# BigClown_GPS_Teseo-LIV3F_module_v1_0.net
KiCad netlist of a schematic drawn in EAGLE
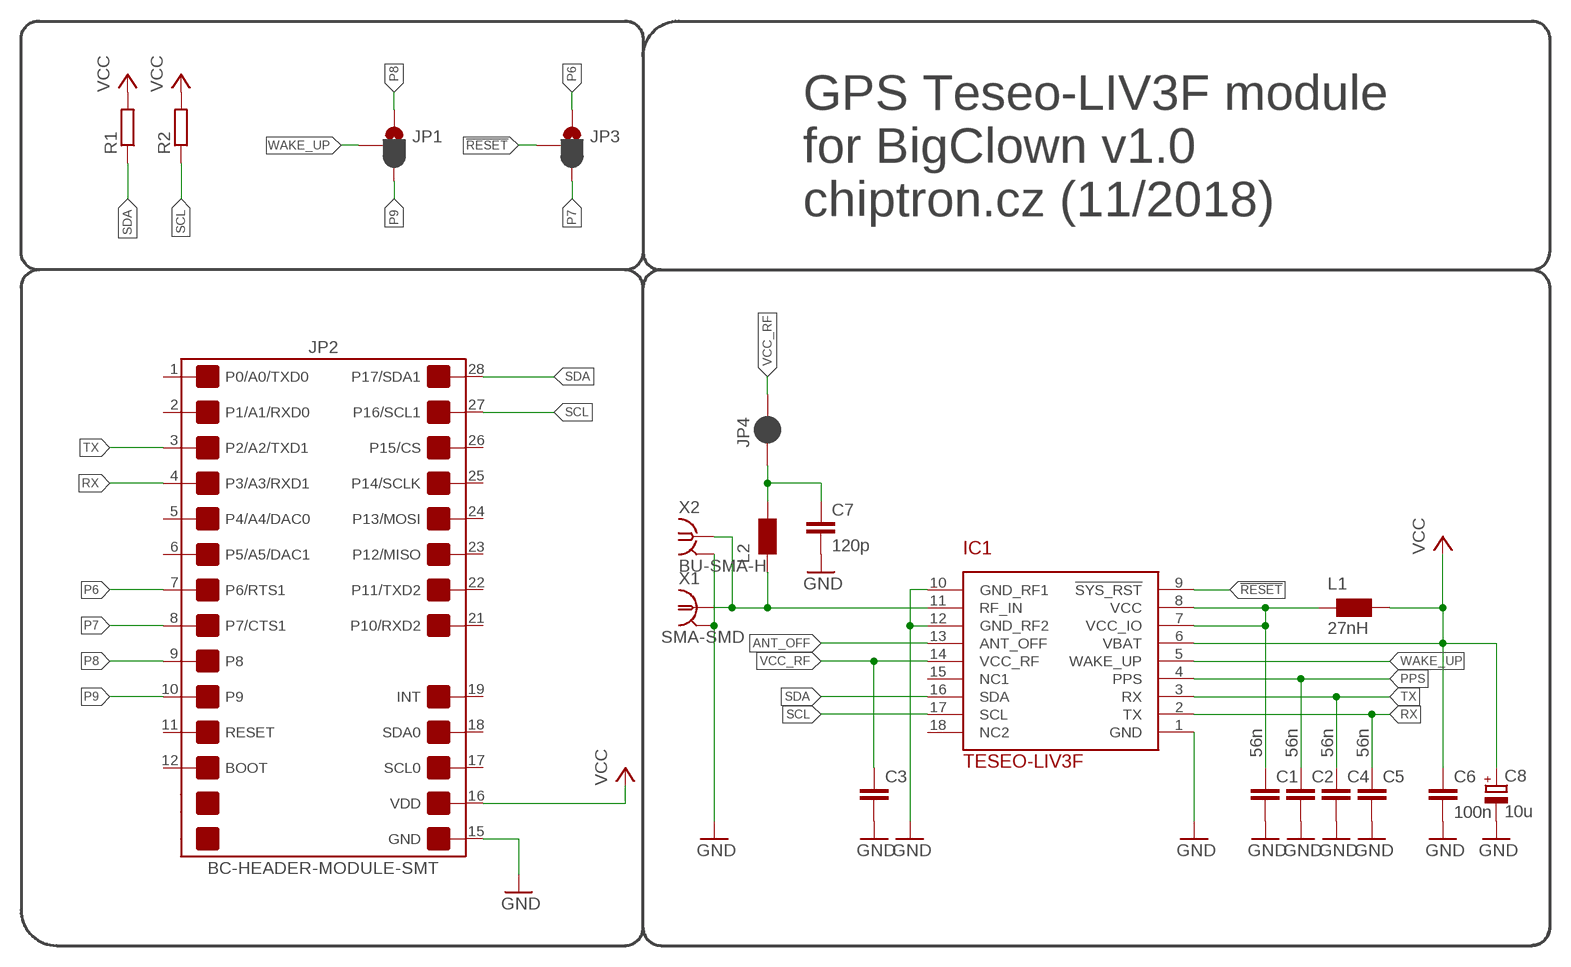
[diagram p0: schematic, sheet 1]

(export (version "E")
  (design (tool "Eeschema 10.0.6"))
  (components
    (comp (ref "C1")
      (value "56n")
      (footprint "eagle-import:C0805")
      (libsource (lib "eagle-import") (part "C-EUC0805"))
    )
    (comp (ref "C2")
      (value "56n")
      (footprint "eagle-import:C0805")
      (libsource (lib "eagle-import") (part "C-EUC0805"))
    )
    (comp (ref "C3")
      (value "C-EUC0805")
      (footprint "eagle-import:C0805")
      (libsource (lib "eagle-import") (part "C-EUC0805"))
    )
    (comp (ref "C4")
      (value "56n")
      (footprint "eagle-import:C0805")
      (libsource (lib "eagle-import") (part "C-EUC0805"))
    )
    (comp (ref "C5")
      (value "56n")
      (footprint "eagle-import:C0805")
      (libsource (lib "eagle-import") (part "C-EUC0805"))
    )
    (comp (ref "C6")
      (value "100n")
      (footprint "eagle-import:C0805")
      (libsource (lib "eagle-import") (part "C-EUC0805"))
    )
    (comp (ref "C7")
      (value "120p")
      (footprint "eagle-import:C0805")
      (libsource (lib "eagle-import") (part "C-EUC0805"))
    )
    (comp (ref "C8")
      (value "10u")
      (footprint "eagle-import:SMC_B")
      (libsource (lib "eagle-import") (part "CPOL-EUSMCB"))
    )
    (comp (ref "IC1")
      (value "TESEO-LIV3F")
      (footprint "eagle-import:TESEO-LIV3F")
      (libsource (lib "eagle-import") (part "TESEO-LIV3F"))
    )
    (comp (ref "JP1")
      (value "JUMPER-SMT_3_1-NC_PASTE_SILK")
      (footprint "eagle-import:SMT-JUMPER_3_1-NC_PASTE_SILK")
      (libsource (lib "eagle-import") (part "JUMPER-SMT_3_1-NC_PASTE_SILK"))
    )
    (comp (ref "JP2")
      (value "BC-HEADER-MODULE-SMT")
      (footprint "eagle-import:BC-HEADER-MODULE-SMT")
      (libsource (lib "eagle-import") (part "BC-HEADER-MODULE-SMT"))
    )
    (comp (ref "JP3")
      (value "JUMPER-SMT_3_1-NC_PASTE_SILK")
      (footprint "eagle-import:SMT-JUMPER_3_1-NC_PASTE_SILK")
      (libsource (lib "eagle-import") (part "JUMPER-SMT_3_1-NC_PASTE_SILK"))
    )
    (comp (ref "JP4")
      (value "JUMPER-SMT_2_NC_PASTE_SILK")
      (footprint "eagle-import:SMT-JUMPER_2_NC_PASTE_SILK")
      (libsource (lib "eagle-import") (part "JUMPER-SMT_2_NC_PASTE_SILK"))
    )
    (comp (ref "L1")
      (value "27nH")
      (footprint "eagle-import:0805")
      (libsource (lib "eagle-import") (part "WE-MK_0805"))
    )
    (comp (ref "L2")
      (value "33nF")
      (footprint "eagle-import:0805")
      (libsource (lib "eagle-import") (part "WE-MK_0805"))
    )
    (comp (ref "R1")
      (value "R-EU_M0805")
      (footprint "eagle-import:M0805")
      (libsource (lib "eagle-import") (part "R-EU_M0805"))
    )
    (comp (ref "R2")
      (value "R-EU_M0805")
      (footprint "eagle-import:M0805")
      (libsource (lib "eagle-import") (part "R-EU_M0805"))
    )
    (comp (ref "X1")
      (value "SMA-SMD")
      (footprint "eagle-import:SMA-SMD")
      (libsource (lib "eagle-import") (part "SMA-SMD"))
    )
    (comp (ref "X2")
      (value "BU-SMA-H")
      (footprint "eagle-import:BU-SMA-H")
      (libsource (lib "eagle-import") (part "BU-SMA-H"))
    )
  )
  (nets
    (net (code "1") (name "/~{RESET}") (class "Default")
      (node (ref "IC1") (pin "9") (pinfunction "~{SYS_RST}_9") (pintype "bidirectional"))
      (node (ref "JP3") (pin "2") (pinfunction "2_2") (pintype "passive"))
    )
    (net (code "2") (name "ANT_OFF") (class "Default")
      (node (ref "IC1") (pin "13") (pinfunction "ANT_OFF_13") (pintype "output"))
    )
    (net (code "3") (name "GND") (class "Default")
      (node (ref "C1") (pin "2") (pinfunction "2_2") (pintype "passive"))
      (node (ref "C2") (pin "2") (pinfunction "2_2") (pintype "passive"))
      (node (ref "C3") (pin "2") (pinfunction "2_2") (pintype "passive"))
      (node (ref "C4") (pin "2") (pinfunction "2_2") (pintype "passive"))
      (node (ref "C5") (pin "2") (pinfunction "2_2") (pintype "passive"))
      (node (ref "C6") (pin "2") (pinfunction "2_2") (pintype "passive"))
      (node (ref "C7") (pin "2") (pinfunction "2_2") (pintype "passive"))
      (node (ref "C8") (pin "-") (pinfunction "-_-") (pintype "passive"))
      (node (ref "IC1") (pin "1") (pinfunction "GND_1") (pintype "power_in"))
      (node (ref "IC1") (pin "10") (pinfunction "GND_RF1_10") (pintype "power_in"))
      (node (ref "IC1") (pin "12") (pinfunction "GND_RF2_12") (pintype "power_in"))
      (node (ref "JP2") (pin "15") (pinfunction "GND_15") (pintype "passive"))
      (node (ref "X1") (pin "2@1") (pinfunction "2_2@1") (pintype "passive"))
      (node (ref "X1") (pin "2@2") (pinfunction "2_2@2") (pintype "passive"))
      (node (ref "X1") (pin "2@3") (pinfunction "2_2@3") (pintype "passive"))
      (node (ref "X1") (pin "2@4") (pinfunction "2_2@4") (pintype "passive"))
      (node (ref "X1") (pin "2@5") (pinfunction "2_2@5") (pintype "passive"))
      (node (ref "X1") (pin "2@6") (pinfunction "2_2@6") (pintype "passive"))
      (node (ref "X2") (pin "2") (pinfunction "2_2") (pintype "passive"))
      (node (ref "X2") (pin "3") (pinfunction "2_3") (pintype "passive"))
      (node (ref "X2") (pin "4") (pinfunction "2_4") (pintype "passive"))
      (node (ref "X2") (pin "5") (pinfunction "2_5") (pintype "passive"))
    )
    (net (code "4") (name "Net-(C7-Pad1)") (class "Default")
      (node (ref "C7") (pin "1") (pinfunction "1_1") (pintype "passive"))
      (node (ref "JP4") (pin "1") (pinfunction "1_1") (pintype "passive"))
      (node (ref "L2") (pin "2") (pinfunction "2_2") (pintype "passive"))
    )
    (net (code "5") (name "Net-(IC1-RF_IN)") (class "Default")
      (node (ref "IC1") (pin "11") (pinfunction "RF_IN_11") (pintype "input"))
      (node (ref "L2") (pin "1") (pinfunction "1_1") (pintype "passive"))
      (node (ref "X1") (pin "1") (pinfunction "1_1") (pintype "passive"))
      (node (ref "X2") (pin "1") (pinfunction "1_1") (pintype "passive"))
    )
    (net (code "6") (name "Net-(IC1-VCC)") (class "Default")
      (node (ref "C1") (pin "1") (pinfunction "1_1") (pintype "passive"))
      (node (ref "IC1") (pin "7") (pinfunction "VCC_IO_7") (pintype "power_in"))
      (node (ref "IC1") (pin "8") (pinfunction "VCC_8") (pintype "power_in"))
      (node (ref "L1") (pin "1") (pinfunction "1_1") (pintype "passive"))
    )
    (net (code "7") (name "P6") (class "Default")
      (node (ref "JP2") (pin "7") (pinfunction "P6/RTS1_7") (pintype "passive"))
      (node (ref "JP3") (pin "1") (pinfunction "1_1") (pintype "passive"))
    )
    (net (code "8") (name "P7") (class "Default")
      (node (ref "JP2") (pin "8") (pinfunction "P7/CTS1_8") (pintype "passive"))
      (node (ref "JP3") (pin "3") (pinfunction "3_3") (pintype "passive"))
    )
    (net (code "9") (name "P8") (class "Default")
      (node (ref "JP1") (pin "1") (pinfunction "1_1") (pintype "passive"))
      (node (ref "JP2") (pin "9") (pinfunction "P8_9") (pintype "passive"))
    )
    (net (code "10") (name "P9") (class "Default")
      (node (ref "JP1") (pin "3") (pinfunction "3_3") (pintype "passive"))
      (node (ref "JP2") (pin "10") (pinfunction "P9_10") (pintype "passive"))
    )
    (net (code "11") (name "PPS") (class "Default")
      (node (ref "C2") (pin "1") (pinfunction "1_1") (pintype "passive"))
      (node (ref "IC1") (pin "4") (pinfunction "PPS_4") (pintype "output"))
    )
    (net (code "12") (name "RX") (class "Default")
      (node (ref "C5") (pin "1") (pinfunction "1_1") (pintype "passive"))
      (node (ref "IC1") (pin "2") (pinfunction "TX_2") (pintype "bidirectional"))
      (node (ref "JP2") (pin "4") (pinfunction "P3/A3/RXD1_4") (pintype "passive"))
    )
    (net (code "13") (name "SCL") (class "Default")
      (node (ref "IC1") (pin "17") (pinfunction "SCL_17") (pintype "bidirectional"))
      (node (ref "JP2") (pin "27") (pinfunction "P16/SCL1_27") (pintype "passive"))
      (node (ref "R2") (pin "1") (pinfunction "1_1") (pintype "passive"))
    )
    (net (code "14") (name "SDA") (class "Default")
      (node (ref "IC1") (pin "16") (pinfunction "SDA_16") (pintype "bidirectional"))
      (node (ref "JP2") (pin "28") (pinfunction "P17/SDA1_28") (pintype "passive"))
      (node (ref "R1") (pin "1") (pinfunction "1_1") (pintype "passive"))
    )
    (net (code "15") (name "TX") (class "Default")
      (node (ref "C4") (pin "1") (pinfunction "1_1") (pintype "passive"))
      (node (ref "IC1") (pin "3") (pinfunction "RX_3") (pintype "bidirectional"))
      (node (ref "JP2") (pin "3") (pinfunction "P2/A2/TXD1_3") (pintype "passive"))
    )
    (net (code "16") (name "VCC") (class "Default")
      (node (ref "C6") (pin "1") (pinfunction "1_1") (pintype "passive"))
      (node (ref "C8") (pin "+") (pinfunction "+_+") (pintype "passive"))
      (node (ref "IC1") (pin "6") (pinfunction "VBAT_6") (pintype "power_in"))
      (node (ref "JP2") (pin "16") (pinfunction "VDD_16") (pintype "passive"))
      (node (ref "L1") (pin "2") (pinfunction "2_2") (pintype "passive"))
      (node (ref "R1") (pin "2") (pinfunction "2_2") (pintype "passive"))
      (node (ref "R2") (pin "2") (pinfunction "2_2") (pintype "passive"))
    )
    (net (code "17") (name "VCC_RF") (class "Default")
      (node (ref "C3") (pin "1") (pinfunction "1_1") (pintype "passive"))
      (node (ref "IC1") (pin "14") (pinfunction "VCC_RF_14") (pintype "power_in"))
      (node (ref "JP4") (pin "2") (pinfunction "2_2") (pintype "passive"))
    )
    (net (code "18") (name "WAKE_UP") (class "Default")
      (node (ref "IC1") (pin "5") (pinfunction "WAKE_UP_5") (pintype "input"))
      (node (ref "JP1") (pin "2") (pinfunction "2_2") (pintype "passive"))
    )
    (net (code "19") (name "unconnected-(IC1-NC1-Pad15)") (class "Default")
      (node (ref "IC1") (pin "15") (pinfunction "NC1_15") (pintype "no_connect"))
    )
    (net (code "20") (name "unconnected-(IC1-NC2-Pad18)") (class "Default")
      (node (ref "IC1") (pin "18") (pinfunction "NC2_18") (pintype "no_connect"))
    )
    (net (code "21") (name "unconnected-(JP2-BOOT-Pad12)") (class "Default")
      (node (ref "JP2") (pin "12") (pinfunction "BOOT_12") (pintype "passive"))
    )
    (net (code "22") (name "unconnected-(JP2-INT-Pad19)") (class "Default")
      (node (ref "JP2") (pin "19") (pinfunction "INT_19") (pintype "passive"))
    )
    (net (code "23") (name "unconnected-(JP2-P0{slash}A0{slash}TXD0-Pad1)") (class "Default")
      (node (ref "JP2") (pin "1") (pinfunction "P0/A0/TXD0_1") (pintype "passive"))
    )
    (net (code "24") (name "unconnected-(JP2-P1{slash}A1{slash}RXD0-Pad2)") (class "Default")
      (node (ref "JP2") (pin "2") (pinfunction "P1/A1/RXD0_2") (pintype "passive"))
    )
    (net (code "25") (name "unconnected-(JP2-P4{slash}A4{slash}DAC0-Pad5)") (class "Default")
      (node (ref "JP2") (pin "5") (pinfunction "P4/A4/DAC0_5") (pintype "passive"))
    )
    (net (code "26") (name "unconnected-(JP2-P5{slash}A5{slash}DAC1-Pad6)") (class "Default")
      (node (ref "JP2") (pin "6") (pinfunction "P5/A5/DAC1_6") (pintype "passive"))
    )
    (net (code "27") (name "unconnected-(JP2-P10{slash}RXD2-Pad21)") (class "Default")
      (node (ref "JP2") (pin "21") (pinfunction "P10/RXD2_21") (pintype "passive"))
    )
    (net (code "28") (name "unconnected-(JP2-P11{slash}TXD2-Pad22)") (class "Default")
      (node (ref "JP2") (pin "22") (pinfunction "P11/TXD2_22") (pintype "passive"))
    )
    (net (code "29") (name "unconnected-(JP2-P12{slash}MISO-Pad23)") (class "Default")
      (node (ref "JP2") (pin "23") (pinfunction "P12/MISO_23") (pintype "passive"))
    )
    (net (code "30") (name "unconnected-(JP2-P13{slash}MOSI-Pad24)") (class "Default")
      (node (ref "JP2") (pin "24") (pinfunction "P13/MOSI_24") (pintype "passive"))
    )
    (net (code "31") (name "unconnected-(JP2-P14{slash}SCLK-Pad25)") (class "Default")
      (node (ref "JP2") (pin "25") (pinfunction "P14/SCLK_25") (pintype "passive"))
    )
    (net (code "32") (name "unconnected-(JP2-P15{slash}CS-Pad26)") (class "Default")
      (node (ref "JP2") (pin "26") (pinfunction "P15/CS_26") (pintype "passive"))
    )
    (net (code "33") (name "unconnected-(JP2-RESET-Pad11)") (class "Default")
      (node (ref "JP2") (pin "11") (pinfunction "RESET_11") (pintype "passive"))
    )
    (net (code "34") (name "unconnected-(JP2-SCL0-Pad17)") (class "Default")
      (node (ref "JP2") (pin "17") (pinfunction "SCL0_17") (pintype "passive"))
    )
    (net (code "35") (name "unconnected-(JP2-SDA0-Pad18)") (class "Default")
      (node (ref "JP2") (pin "18") (pinfunction "SDA0_18") (pintype "passive"))
    )
  )
)
